# T-bar_Breakout.net
KiCad netlist of a schematic drawn in EAGLE
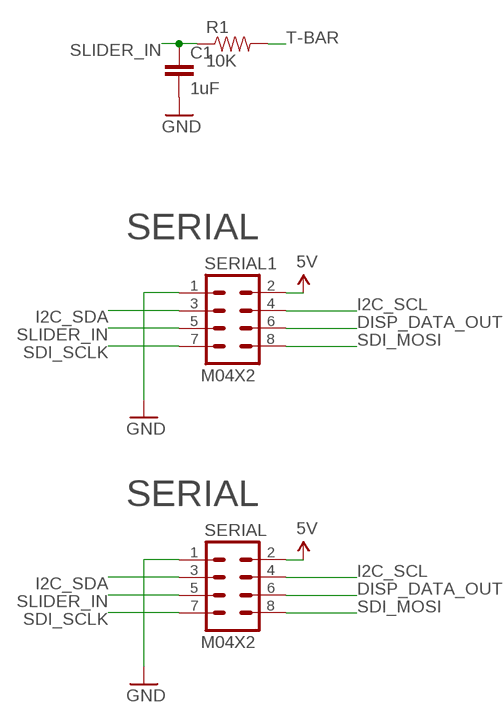
[diagram p0: schematic, sheet 1]

(export (version "E")
  (design (tool "Eeschema 10.0.6"))
  (components
    (comp (ref "C1")
      (value "1uF")
      (footprint "eagle-import:0603-CAP")
      (libsource (lib "eagle-import") (part "CAP0603-CAP"))
    )
    (comp (ref "R1")
      (value "10K")
      (footprint "eagle-import:0603-RES")
      (libsource (lib "eagle-import") (part "RESISTOR0603-RES"))
    )
    (comp (ref "SERIAL")
      (value "M04X2")
      (footprint "eagle-import:2X4")
      (libsource (lib "eagle-import") (part "M04X2"))
    )
    (comp (ref "SERIAL1")
      (value "M04X2")
      (footprint "eagle-import:2X4")
      (libsource (lib "eagle-import") (part "M04X2"))
    )
  )
  (nets
    (net (code "1") (name "/DISP_DATA_OUT") (class "Default")
      (node (ref "SERIAL") (pin "6") (pinfunction "6_6") (pintype "passive"))
      (node (ref "SERIAL1") (pin "6") (pinfunction "6_6") (pintype "passive"))
    )
    (net (code "2") (name "/I2C_SCL") (class "Default")
      (node (ref "SERIAL") (pin "4") (pinfunction "4_4") (pintype "passive"))
      (node (ref "SERIAL1") (pin "4") (pinfunction "4_4") (pintype "passive"))
    )
    (net (code "3") (name "/I2C_SDA") (class "Default")
      (node (ref "SERIAL") (pin "3") (pinfunction "3_3") (pintype "passive"))
      (node (ref "SERIAL1") (pin "3") (pinfunction "3_3") (pintype "passive"))
    )
    (net (code "4") (name "/SDI_MOSI") (class "Default")
      (node (ref "SERIAL") (pin "8") (pinfunction "8_8") (pintype "passive"))
      (node (ref "SERIAL1") (pin "8") (pinfunction "8_8") (pintype "passive"))
    )
    (net (code "5") (name "/SDI_SCLK") (class "Default")
      (node (ref "SERIAL") (pin "7") (pinfunction "7_7") (pintype "passive"))
      (node (ref "SERIAL1") (pin "7") (pinfunction "7_7") (pintype "passive"))
    )
    (net (code "6") (name "/SLIDER_IN") (class "Default")
      (node (ref "C1") (pin "1") (pinfunction "1_1") (pintype "passive"))
      (node (ref "R1") (pin "1") (pinfunction "1_1") (pintype "passive"))
      (node (ref "SERIAL") (pin "5") (pinfunction "5_5") (pintype "passive"))
      (node (ref "SERIAL1") (pin "5") (pinfunction "5_5") (pintype "passive"))
    )
    (net (code "7") (name "/T-BAR") (class "Default")
      (node (ref "R1") (pin "2") (pinfunction "2_2") (pintype "passive"))
    )
    (net (code "8") (name "5V") (class "Default")
      (node (ref "SERIAL") (pin "2") (pinfunction "2_2") (pintype "passive"))
      (node (ref "SERIAL1") (pin "2") (pinfunction "2_2") (pintype "passive"))
    )
    (net (code "9") (name "GND") (class "Default")
      (node (ref "C1") (pin "2") (pinfunction "2_2") (pintype "passive"))
      (node (ref "SERIAL") (pin "1") (pinfunction "1_1") (pintype "passive"))
      (node (ref "SERIAL1") (pin "1") (pinfunction "1_1") (pintype "passive"))
    )
  )
)
